# Adafruit_LIS3DH.net
KiCad netlist of a schematic drawn in EAGLE
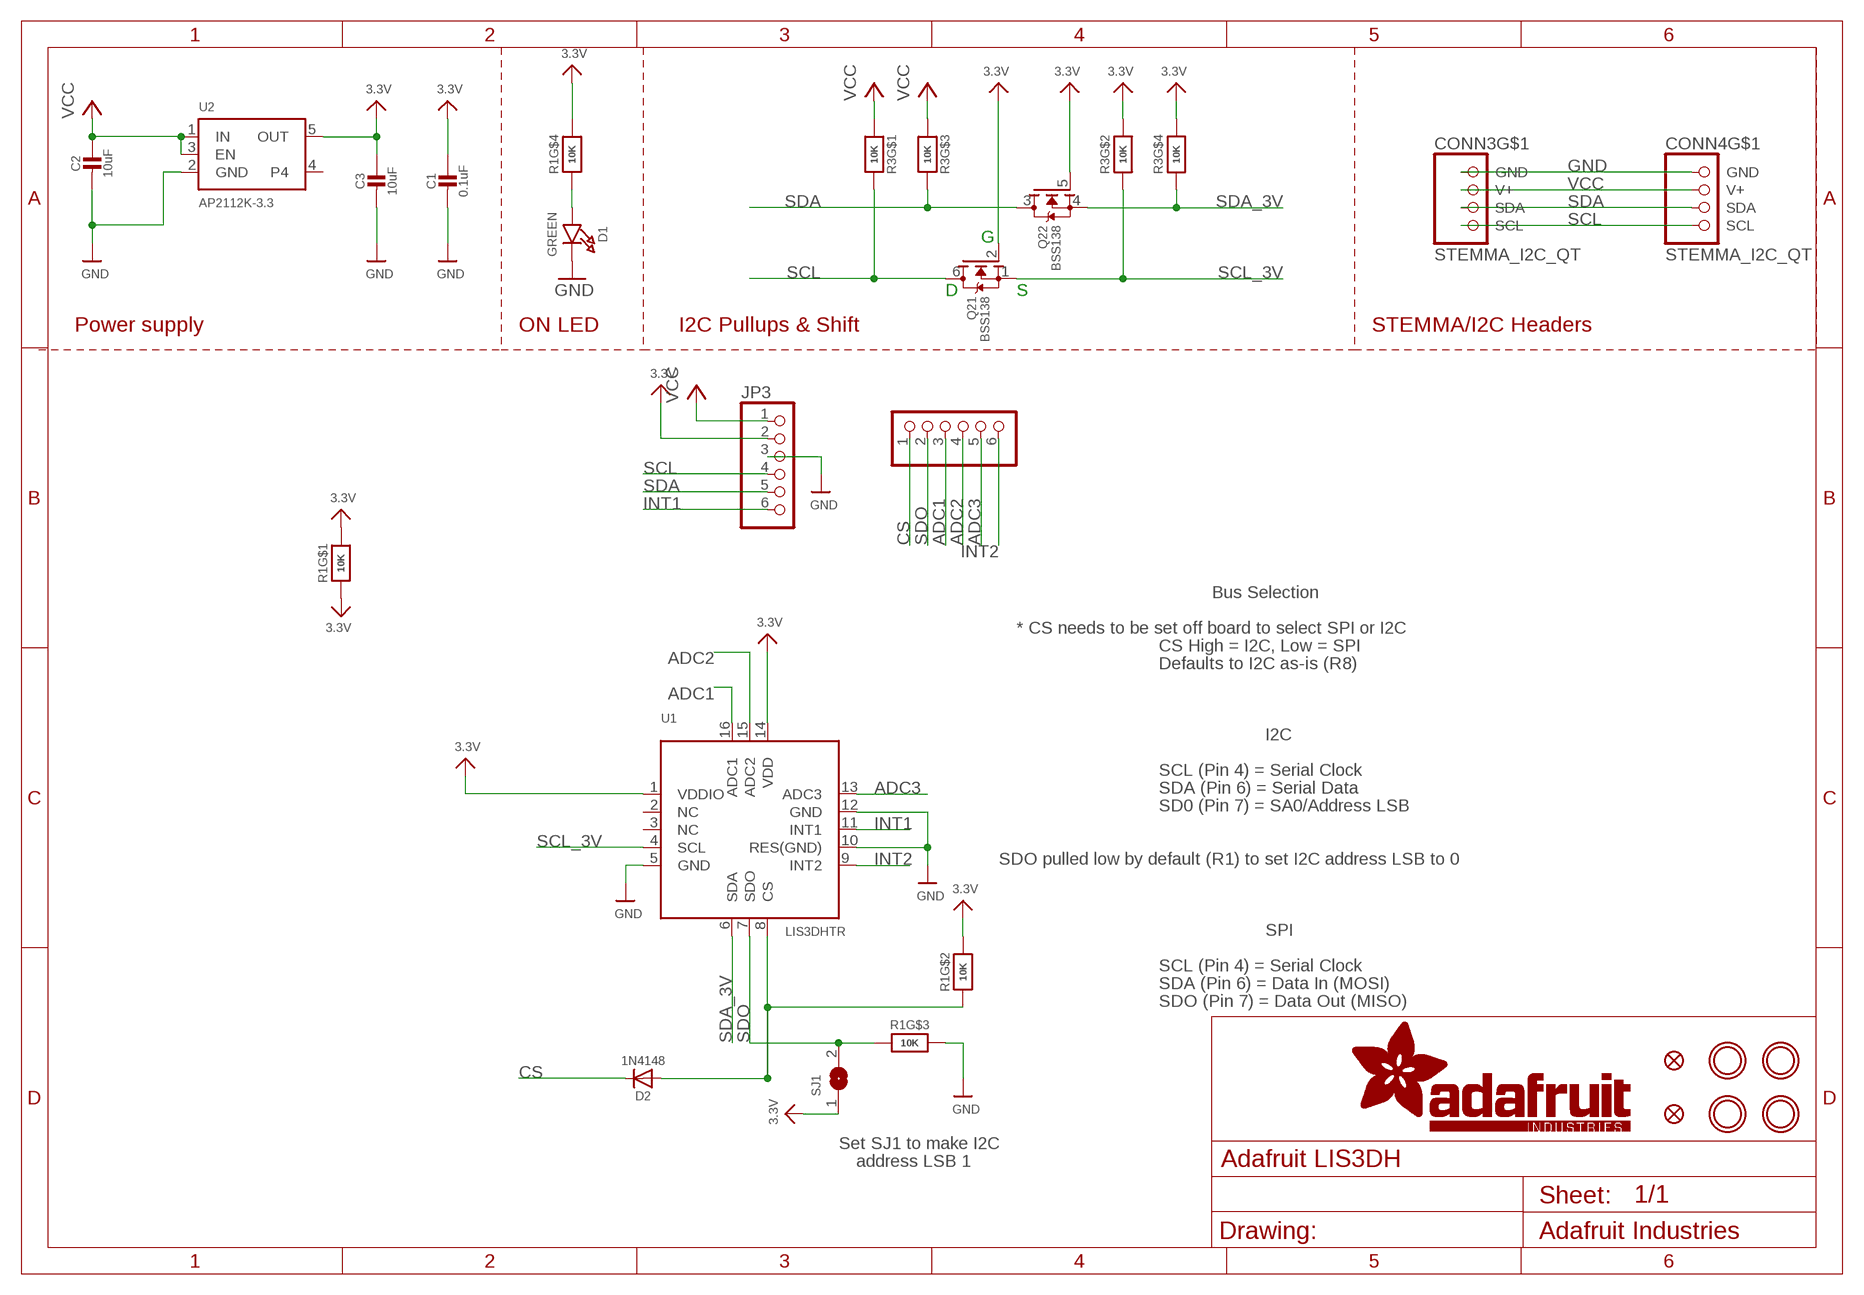
[diagram p0: schematic, sheet 1]

(export (version "E")
  (design (tool "Eeschema 10.0.6"))
  (components
    (comp (ref "C1")
      (value "0.1uF")
      (footprint "eagle-import:0603-NO")
      (libsource (lib "eagle-import") (part "CAP_CERAMIC0603_NO"))
    )
    (comp (ref "C2")
      (value "10uF")
      (footprint "eagle-import:0805-NO")
      (libsource (lib "eagle-import") (part "CAP_CERAMIC0805-NOOUTLINE"))
    )
    (comp (ref "C3")
      (value "10uF")
      (footprint "eagle-import:0805-NO")
      (libsource (lib "eagle-import") (part "CAP_CERAMIC0805-NOOUTLINE"))
    )
    (comp (ref "CONN3")
      (value "STEMMA_I2C_QT")
      (footprint "eagle-import:JST_SH4")
      (libsource (lib "eagle-import") (part "STEMMA_I2C_QT"))
    )
    (comp (ref "CONN4")
      (value "STEMMA_I2C_QT")
      (footprint "eagle-import:JST_SH4")
      (libsource (lib "eagle-import") (part "STEMMA_I2C_QT"))
    )
    (comp (ref "D1")
      (value "GREEN")
      (footprint "eagle-import:CHIPLED_0603_NOOUTLINE")
      (libsource (lib "eagle-import") (part "LED0603_NOOUTLINE"))
    )
    (comp (ref "D2")
      (value "1N4148")
      (footprint "eagle-import:SOD-323")
      (libsource (lib "eagle-import") (part "DIODESOD-323"))
    )
    (comp (ref "FID3")
      (value "FIDUCIAL_1MM")
      (footprint "eagle-import:FIDUCIAL_1MM")
      (libsource (lib "eagle-import") (part "FIDUCIAL_1MM"))
    )
    (comp (ref "FID4")
      (value "FIDUCIAL_1MM")
      (footprint "eagle-import:FIDUCIAL_1MM")
      (libsource (lib "eagle-import") (part "FIDUCIAL_1MM"))
    )
    (comp (ref "JP2")
      (value "HEADER-1X670MIL")
      (footprint "eagle-import:1X06_ROUND_70")
      (libsource (lib "eagle-import") (part "HEADER-1X670MIL"))
    )
    (comp (ref "JP3")
      (value "HEADER-1X670MIL")
      (footprint "eagle-import:1X06_ROUND_70")
      (libsource (lib "eagle-import") (part "HEADER-1X670MIL"))
    )
    (comp (ref "Q2")
      (value "BSS138")
      (footprint "eagle-import:SOT363")
      (libsource (lib "eagle-import") (part "MOSFET-N_DUAL"))
    )
    (comp (ref "R1")
      (value "10K")
      (footprint "eagle-import:RESPACK_4X0603")
      (libsource (lib "eagle-import") (part "RESISTOR_4PACK"))
    )
    (comp (ref "R3")
      (value "10K")
      (footprint "eagle-import:RESPACK_4X0603")
      (libsource (lib "eagle-import") (part "RESISTOR_4PACK"))
    )
    (comp (ref "SJ1")
      (value "SOLDERJUMPER")
      (footprint "eagle-import:SOLDERJUMPER_ARROW_NOPASTE")
      (libsource (lib "eagle-import") (part "SOLDERJUMPER"))
    )
    (comp (ref "U$1")
      (value "MOUNTINGHOLE2.5")
      (footprint "eagle-import:MOUNTINGHOLE_2.5_PLATED")
      (libsource (lib "eagle-import") (part "MOUNTINGHOLE2.5"))
    )
    (comp (ref "U$17")
      (value "MOUNTINGHOLE2.5")
      (footprint "eagle-import:MOUNTINGHOLE_2.5_PLATED")
      (libsource (lib "eagle-import") (part "MOUNTINGHOLE2.5"))
    )
    (comp (ref "U$19")
      (value "MOUNTINGHOLE2.5")
      (footprint "eagle-import:MOUNTINGHOLE_2.5_PLATED")
      (libsource (lib "eagle-import") (part "MOUNTINGHOLE2.5"))
    )
    (comp (ref "U$21")
      (value "MOUNTINGHOLE2.5")
      (footprint "eagle-import:MOUNTINGHOLE_2.5_PLATED")
      (libsource (lib "eagle-import") (part "MOUNTINGHOLE2.5"))
    )
    (comp (ref "U1")
      (value "LIS3DHTR")
      (footprint "eagle-import:LGA16_3X3MM")
      (libsource (lib "eagle-import") (part "ACCEL_LIS3DHTR"))
    )
    (comp (ref "U2")
      (value "AP2112K-3.3")
      (footprint "eagle-import:SOT23-5")
      (libsource (lib "eagle-import") (part "VREG_SOT23-5"))
    )
  )
  (nets
    (net (code "1") (name "/ADC1") (class "Default")
      (node (ref "JP2") (pin "3") (pinfunction "3_3") (pintype "passive"))
      (node (ref "U1") (pin "16") (pinfunction "ADC1_16") (pintype "input"))
    )
    (net (code "2") (name "/ADC2") (class "Default")
      (node (ref "JP2") (pin "4") (pinfunction "4_4") (pintype "passive"))
      (node (ref "U1") (pin "15") (pinfunction "ADC2_15") (pintype "input"))
    )
    (net (code "3") (name "/ADC3") (class "Default")
      (node (ref "JP2") (pin "5") (pinfunction "5_5") (pintype "passive"))
      (node (ref "U1") (pin "13") (pinfunction "ADC3_13") (pintype "input"))
    )
    (net (code "4") (name "/CS") (class "Default")
      (node (ref "D2") (pin "C") (pinfunction "C_C") (pintype "passive"))
      (node (ref "JP2") (pin "1") (pinfunction "1_1") (pintype "passive"))
    )
    (net (code "5") (name "/INT1") (class "Default")
      (node (ref "JP3") (pin "6") (pinfunction "6_6") (pintype "passive"))
      (node (ref "U1") (pin "11") (pinfunction "INT1_11") (pintype "output"))
    )
    (net (code "6") (name "/INT2") (class "Default")
      (node (ref "JP2") (pin "6") (pinfunction "6_6") (pintype "passive"))
      (node (ref "U1") (pin "9") (pinfunction "INT2_9") (pintype "output"))
    )
    (net (code "7") (name "/SCL") (class "Default")
      (node (ref "CONN3") (pin "4") (pinfunction "SCL_4") (pintype "passive"))
      (node (ref "CONN4") (pin "4") (pinfunction "SCL_4") (pintype "passive"))
      (node (ref "JP3") (pin "4") (pinfunction "4_4") (pintype "passive"))
      (node (ref "Q2") (pin "6") (pinfunction "D_6") (pintype "bidirectional"))
      (node (ref "R3") (pin "8") (pinfunction "2_8") (pintype "passive"))
    )
    (net (code "8") (name "/SCL_3V") (class "Default")
      (node (ref "Q2") (pin "1") (pinfunction "S_1") (pintype "bidirectional"))
      (node (ref "R3") (pin "7") (pinfunction "2_7") (pintype "passive"))
      (node (ref "U1") (pin "4") (pinfunction "SCL_4") (pintype "bidirectional"))
    )
    (net (code "9") (name "/SDA") (class "Default")
      (node (ref "CONN3") (pin "3") (pinfunction "SDA_3") (pintype "passive"))
      (node (ref "CONN4") (pin "3") (pinfunction "SDA_3") (pintype "passive"))
      (node (ref "JP3") (pin "5") (pinfunction "5_5") (pintype "passive"))
      (node (ref "Q2") (pin "3") (pinfunction "D_3") (pintype "bidirectional"))
      (node (ref "R3") (pin "6") (pinfunction "2_6") (pintype "passive"))
    )
    (net (code "10") (name "/SDA_3V") (class "Default")
      (node (ref "Q2") (pin "4") (pinfunction "S_4") (pintype "bidirectional"))
      (node (ref "R3") (pin "5") (pinfunction "2_5") (pintype "passive"))
      (node (ref "U1") (pin "6") (pinfunction "SDA_6") (pintype "bidirectional"))
    )
    (net (code "11") (name "/SDO") (class "Default")
      (node (ref "JP2") (pin "2") (pinfunction "2_2") (pintype "passive"))
      (node (ref "R1") (pin "3") (pinfunction "1_3") (pintype "passive"))
      (node (ref "SJ1") (pin "2") (pinfunction "2_2") (pintype "passive"))
      (node (ref "U1") (pin "7") (pinfunction "SDO_7") (pintype "bidirectional"))
    )
    (net (code "12") (name "3.3V") (class "Default")
      (node (ref "C1") (pin "1") (pinfunction "1_1") (pintype "passive"))
      (node (ref "C3") (pin "1") (pinfunction "1_1") (pintype "passive"))
      (node (ref "JP3") (pin "2") (pinfunction "2_2") (pintype "passive"))
      (node (ref "Q2") (pin "2") (pinfunction "G_2") (pintype "bidirectional"))
      (node (ref "Q2") (pin "5") (pinfunction "G_5") (pintype "bidirectional"))
      (node (ref "R1") (pin "1") (pinfunction "1_1") (pintype "passive"))
      (node (ref "R1") (pin "5") (pinfunction "2_5") (pintype "passive"))
      (node (ref "R1") (pin "7") (pinfunction "2_7") (pintype "passive"))
      (node (ref "R1") (pin "8") (pinfunction "2_8") (pintype "passive"))
      (node (ref "R3") (pin "2") (pinfunction "1_2") (pintype "passive"))
      (node (ref "R3") (pin "4") (pinfunction "1_4") (pintype "passive"))
      (node (ref "SJ1") (pin "1") (pinfunction "1_1") (pintype "passive"))
      (node (ref "U1") (pin "1") (pinfunction "VDDIO_1") (pintype "power_in"))
      (node (ref "U1") (pin "14") (pinfunction "VDD_14") (pintype "power_in"))
      (node (ref "U2") (pin "5") (pinfunction "OUT_5") (pintype "power_in"))
    )
    (net (code "13") (name "GND") (class "Default")
      (node (ref "C1") (pin "2") (pinfunction "2_2") (pintype "passive"))
      (node (ref "C2") (pin "2") (pinfunction "2_2") (pintype "passive"))
      (node (ref "C3") (pin "2") (pinfunction "2_2") (pintype "passive"))
      (node (ref "CONN3") (pin "1") (pinfunction "GND_1") (pintype "passive"))
      (node (ref "CONN4") (pin "1") (pinfunction "GND_1") (pintype "passive"))
      (node (ref "D1") (pin "C") (pinfunction "C_C") (pintype "passive"))
      (node (ref "JP3") (pin "3") (pinfunction "3_3") (pintype "passive"))
      (node (ref "R1") (pin "6") (pinfunction "2_6") (pintype "passive"))
      (node (ref "U1") (pin "10") (pinfunction "RES(GND)_10") (pintype "bidirectional"))
      (node (ref "U1") (pin "12") (pinfunction "GND_12") (pintype "power_in"))
      (node (ref "U1") (pin "5") (pinfunction "GND_5") (pintype "power_in"))
      (node (ref "U2") (pin "2") (pinfunction "GND_2") (pintype "power_in"))
    )
    (net (code "14") (name "Net-(R1B-1)") (class "Default")
      (node (ref "D2") (pin "A") (pinfunction "A_A") (pintype "passive"))
      (node (ref "R1") (pin "2") (pinfunction "1_2") (pintype "passive"))
      (node (ref "U1") (pin "8") (pinfunction "CS_8") (pintype "input"))
    )
    (net (code "15") (name "Net-(R1D-1)") (class "Default")
      (node (ref "D1") (pin "A") (pinfunction "A_A") (pintype "passive"))
      (node (ref "R1") (pin "4") (pinfunction "1_4") (pintype "passive"))
    )
    (net (code "16") (name "VCC") (class "Default")
      (node (ref "C2") (pin "1") (pinfunction "1_1") (pintype "passive"))
      (node (ref "CONN3") (pin "2") (pinfunction "V+_2") (pintype "passive"))
      (node (ref "CONN4") (pin "2") (pinfunction "V+_2") (pintype "passive"))
      (node (ref "JP3") (pin "1") (pinfunction "1_1") (pintype "passive"))
      (node (ref "R3") (pin "1") (pinfunction "1_1") (pintype "passive"))
      (node (ref "R3") (pin "3") (pinfunction "1_3") (pintype "passive"))
      (node (ref "U2") (pin "1") (pinfunction "IN_1") (pintype "power_in"))
      (node (ref "U2") (pin "3") (pinfunction "EN_3") (pintype "input"))
    )
    (net (code "17") (name "unconnected-(U1-NC-Pad2)") (class "Default")
      (node (ref "U1") (pin "2") (pinfunction "NC_2") (pintype "no_connect"))
    )
    (net (code "18") (name "unconnected-(U1-NC-Pad3)") (class "Default")
      (node (ref "U1") (pin "3") (pinfunction "NC_3") (pintype "no_connect"))
    )
    (net (code "19") (name "unconnected-(U2-P4-Pad4)") (class "Default")
      (node (ref "U2") (pin "4") (pinfunction "P4_4") (pintype "bidirectional"))
    )
  )
)
